# ADC_2CH.net
KiCad netlist of a schematic drawn in Altium Designer
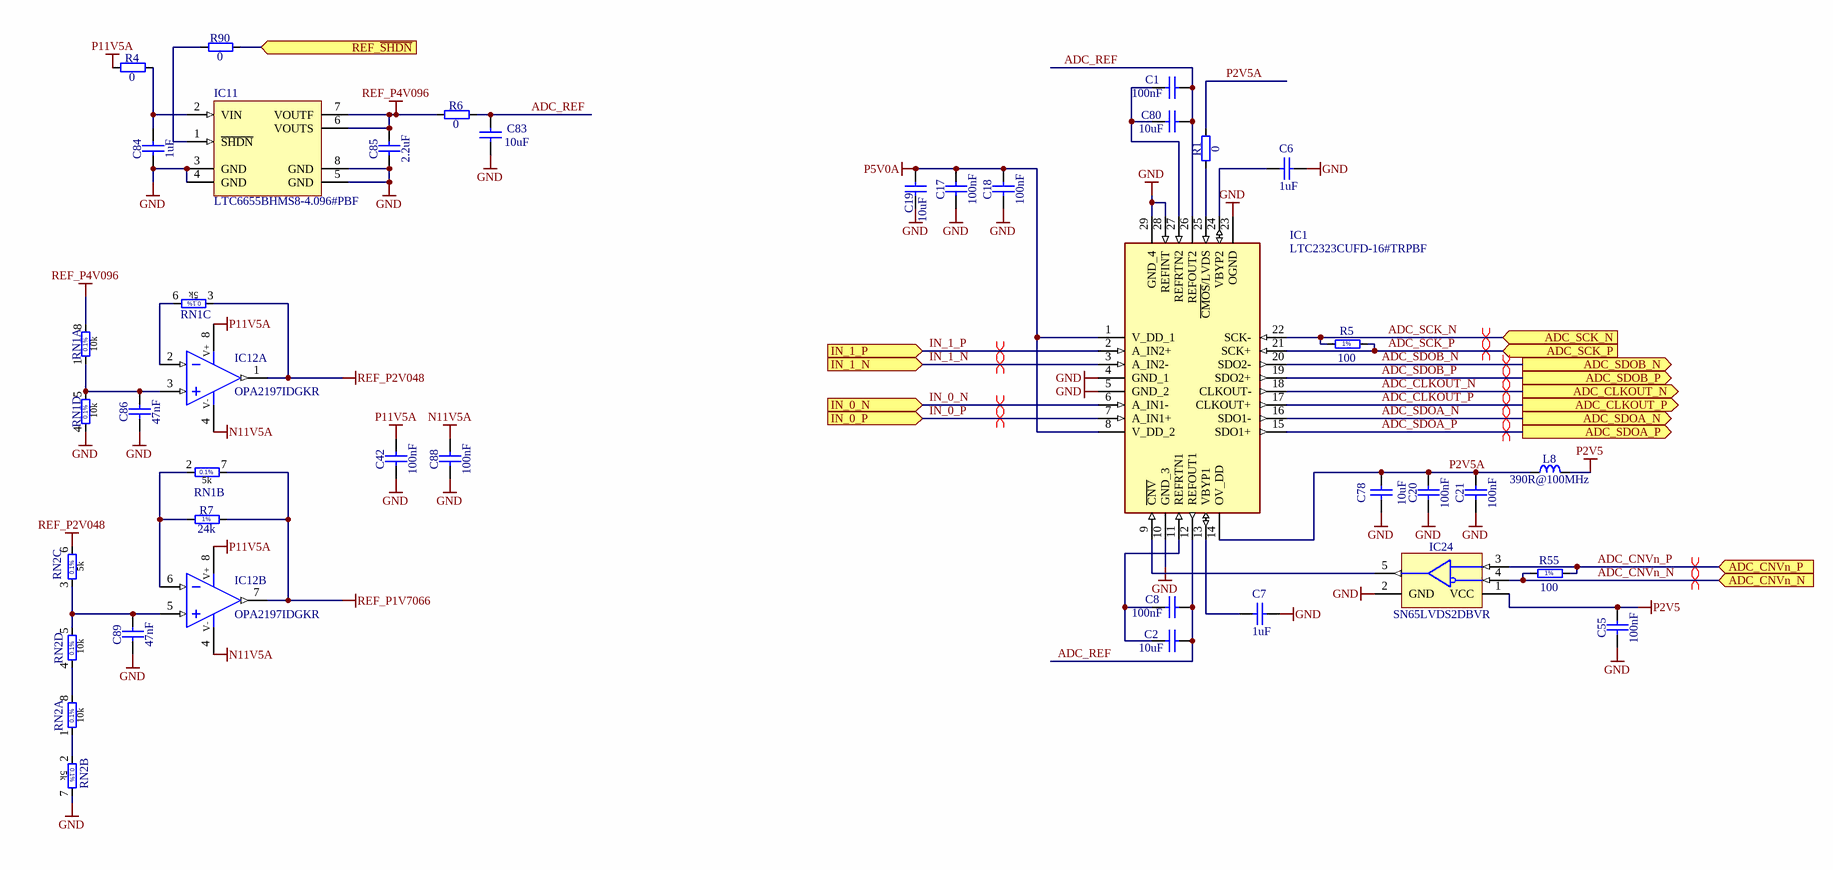
[diagram p0: ADC_2CH.SchDoc]

(export (version "E")
  (design (tool "Eeschema 10.0.6"))
  (components
    (comp (ref "C1")
      (value "100nF")
      (footprint "CAPC1608X87N")
      (description "Non-polarised capacitor")
      (fields
        (field (name "PART NUMBER") "CC0603_100NF_50V_10%_X7R")
        (field (name "VOLTAGE") "50V")
        (field (name "AUTHOR") "CERN DEM JLC")
      )
      (libsource (lib "Capacitors") (part "Capacitor - non polarized"))
    )
    (comp (ref "C2")
      (value "10uF")
      (footprint "CAPC2012X95N")
      (description "Non-polarised capacitor")
      (fields
        (field (name "PART NUMBER") "CC0805_10UF_25V_10%_X5R")
        (field (name "VOLTAGE") "25V")
        (field (name "AUTHOR") "CERN DEM JLC")
      )
      (libsource (lib "Capacitors") (part "Capacitor - non polarized"))
    )
    (comp (ref "C6")
      (value "1uF")
      (footprint "CAPC1608X87N")
      (description "Non-polarised capacitor")
      (fields
        (field (name "PART NUMBER") "CC0603_1UF_25V_10%_X7R")
        (field (name "VOLTAGE") "25V")
        (field (name "AUTHOR") "CERN DEM JLC")
      )
      (libsource (lib "Capacitors") (part "Capacitor - non polarized"))
    )
    (comp (ref "C7")
      (value "1uF")
      (footprint "CAPC1608X87N")
      (description "Non-polarised capacitor")
      (fields
        (field (name "PART NUMBER") "CC0603_1UF_25V_10%_X7R")
        (field (name "VOLTAGE") "25V")
        (field (name "AUTHOR") "CERN DEM JLC")
      )
      (libsource (lib "Capacitors") (part "Capacitor - non polarized"))
    )
    (comp (ref "C8")
      (value "100nF")
      (footprint "CAPC1608X87N")
      (description "Non-polarised capacitor")
      (fields
        (field (name "PART NUMBER") "CC0603_100NF_50V_10%_X7R")
        (field (name "VOLTAGE") "50V")
        (field (name "AUTHOR") "CERN DEM JLC")
      )
      (libsource (lib "Capacitors") (part "Capacitor - non polarized"))
    )
    (comp (ref "C17")
      (value "100nF")
      (footprint "CAPC1608X87N")
      (description "Non-polarised capacitor")
      (fields
        (field (name "PART NUMBER") "CC0603_100NF_50V_10%_X7R")
        (field (name "VOLTAGE") "50V")
        (field (name "AUTHOR") "CERN DEM JLC")
      )
      (libsource (lib "Capacitors") (part "Capacitor - non polarized"))
    )
    (comp (ref "C18")
      (value "100nF")
      (footprint "CAPC1608X87N")
      (description "Non-polarised capacitor")
      (fields
        (field (name "PART NUMBER") "CC0603_100NF_50V_10%_X7R")
        (field (name "VOLTAGE") "50V")
        (field (name "AUTHOR") "CERN DEM JLC")
      )
      (libsource (lib "Capacitors") (part "Capacitor - non polarized"))
    )
    (comp (ref "C19")
      (value "10uF")
      (footprint "CAPC2012X95N")
      (description "Non-polarised capacitor")
      (fields
        (field (name "PART NUMBER") "CC0805_10UF_25V_10%_X5R")
        (field (name "VOLTAGE") "25V")
        (field (name "AUTHOR") "CERN DEM JLC")
      )
      (libsource (lib "Capacitors") (part "Capacitor - non polarized"))
    )
    (comp (ref "C20")
      (value "100nF")
      (footprint "CAPC1608X87N")
      (description "Non-polarised capacitor")
      (fields
        (field (name "PART NUMBER") "CC0603_100NF_50V_10%_X7R")
        (field (name "VOLTAGE") "50V")
        (field (name "AUTHOR") "CERN DEM JLC")
      )
      (libsource (lib "Capacitors") (part "Capacitor - non polarized"))
    )
    (comp (ref "C21")
      (value "100nF")
      (footprint "CAPC1608X87N")
      (description "Non-polarised capacitor")
      (fields
        (field (name "PART NUMBER") "CC0603_100NF_50V_10%_X7R")
        (field (name "VOLTAGE") "50V")
        (field (name "AUTHOR") "CERN DEM JLC")
      )
      (libsource (lib "Capacitors") (part "Capacitor - non polarized"))
    )
    (comp (ref "C42")
      (value "100nF")
      (footprint "CAPC1005X55N")
      (description "Non-polarised capacitor")
      (fields
        (field (name "PART NUMBER") "CC0402_100NF_16V_10%_X5R")
        (field (name "VOLTAGE") "16V")
        (field (name "AUTHOR") "CERN DEM JLC")
      )
      (libsource (lib "Capacitors") (part "Capacitor - non polarized"))
    )
    (comp (ref "C55")
      (value "100nF")
      (footprint "CAPC1608X87N")
      (description "Non-polarised capacitor")
      (fields
        (field (name "PART NUMBER") "CC0603_100NF_50V_10%_X7R")
        (field (name "VOLTAGE") "50V")
        (field (name "AUTHOR") "CERN DEM JLC")
      )
      (libsource (lib "Capacitors") (part "Capacitor - non polarized"))
    )
    (comp (ref "C78")
      (value "10uF")
      (footprint "CAPC2012X95N")
      (description "Non-polarised capacitor")
      (fields
        (field (name "PART NUMBER") "CC0805_10UF_25V_10%_X5R")
        (field (name "VOLTAGE") "25V")
        (field (name "AUTHOR") "CERN DEM JLC")
      )
      (libsource (lib "Capacitors") (part "Capacitor - non polarized"))
    )
    (comp (ref "C80")
      (value "10uF")
      (footprint "CAPC2012X95N")
      (description "Non-polarised capacitor")
      (fields
        (field (name "PART NUMBER") "CC0805_10UF_25V_10%_X5R")
        (field (name "VOLTAGE") "25V")
        (field (name "AUTHOR") "CERN DEM JLC")
      )
      (libsource (lib "Capacitors") (part "Capacitor - non polarized"))
    )
    (comp (ref "C83")
      (value "10uF")
      (footprint "CAPC2012X95N")
      (description "Non-polarised capacitor")
      (fields
        (field (name "PART NUMBER") "CC0805_10UF_25V_10%_X5R")
        (field (name "VOLTAGE") "25V")
        (field (name "AUTHOR") "CERN DEM JLC")
      )
      (libsource (lib "Capacitors") (part "Capacitor - non polarized"))
    )
    (comp (ref "C84")
      (value "1uF")
      (footprint "CAPC1608X87N")
      (description "Non-polarised capacitor")
      (fields
        (field (name "PART NUMBER") "CC0603_1UF_25V_10%_X7R")
        (field (name "VOLTAGE") "25V")
        (field (name "AUTHOR") "CERN DEM JLC")
      )
      (libsource (lib "Capacitors") (part "Capacitor - non polarized"))
    )
    (comp (ref "C85")
      (value "2.2uF")
      (footprint "CAPC1608X87N")
      (description "Non-polarised capacitor")
      (fields
        (field (name "PART NUMBER") "CC0603_2.2UF_16V_10%_X5R")
        (field (name "VOLTAGE") "16V")
        (field (name "AUTHOR") "CERN DEM JLC")
      )
      (libsource (lib "Capacitors") (part "Capacitor - non polarized"))
    )
    (comp (ref "C86")
      (value "47nF")
      (footprint "CAPC2012X135N")
      (description "Non-polarised capacitor")
      (fields
        (field (name "PART NUMBER") "CC0805_47NF_25V_5%_C0G")
        (field (name "VOLTAGE") "25V")
        (field (name "AUTHOR") "CERN DEM JLC")
      )
      (libsource (lib "Capacitors") (part "Capacitor - non polarized"))
    )
    (comp (ref "C88")
      (value "100nF")
      (footprint "CAPC1005X55N")
      (description "Non-polarised capacitor")
      (fields
        (field (name "PART NUMBER") "CC0402_100NF_16V_10%_X5R")
        (field (name "VOLTAGE") "16V")
        (field (name "AUTHOR") "CERN DEM JLC")
      )
      (libsource (lib "Capacitors") (part "Capacitor - non polarized"))
    )
    (comp (ref "C89")
      (value "47nF")
      (footprint "CAPC2012X135N")
      (description "Non-polarised capacitor")
      (fields
        (field (name "PART NUMBER") "CC0805_47NF_25V_5%_C0G")
        (field (name "VOLTAGE") "25V")
        (field (name "AUTHOR") "CERN DEM JLC")
      )
      (libsource (lib "Capacitors") (part "Capacitor - non polarized"))
    )
    (comp (ref "IC1")
      (value "LTC2323CUFD-16#TRPBF")
      (footprint "SamacSys:QFN50P400X500X80-29N")
      (description "Integrated Circuit")
      (libsource (lib "*") (part "LTC2323CUFD-16#TRPBF"))
    )
    (comp (ref "IC11")
      (value "LTC6655BHMS8-4.096#PBF")
      (footprint "SOP65P490X110-8N")
      (description "0.25ppm Noise, Low Drift Precision Buffered Voltage Reference")
      (fields (field (name "MANUFACTURER") "LINEAR TECHNOLOGY") (field (name "AUTHOR") "GK"))
      (libsource (lib "LIBRARY_SCH") (part "REF_LTC6655"))
    )
    (comp (ref "IC12")
      (value "OPA2197IDGKR")
      (footprint "SOP65P490X110-8N")
      (description "36-V, Precision, Rail-to-Rail Input Output, Low Offset Voltage Op Amp 8-VSSOP")
      (fields (field (name "MANUFACTURER") "TEXAS INSTRUMENTS") (field (name "AUTHOR") "GK"))
      (libsource (lib "LIBRARY_SCH") (part "OA_OPA2197IDGKR"))
    )
    (comp (ref "IC24")
      (value "SN65LVDS2DBVR")
      (footprint "SOT95P280X145-5N")
      (description "High-Speed Differential Line Receiver")
      (fields (field (name "MANUFACTURER") "TEXAS INSTRUMENTS") (field (name "AUTHOR") "CERN DEM JLC"))
      (libsource (lib "ICs And Semiconductors") (part "SN65LVDS2DBV"))
    )
    (comp (ref "L8")
      (value "390R@100MHz")
      (footprint "INDC1608X95N")
      (description "Inductor")
      (fields
        (field (name "PART NUMBER") "IND0603_TDK_MPZ1608R391A")
        (field (name "POWER") "1.2A")
        (field (name "AUTHOR") "CERN DEM JLC")
      )
      (libsource (lib "Inductors & Transformers") (part "Inductor"))
    )
    (comp (ref "R1")
      (value "0")
      (footprint "RESC1005X40N")
      (description "Resistor")
      (fields
        (field (name "PART NUMBER") "R0402_0R_JUMPER")
        (field (name "MANUFACTURER") "GENERIC")
        (field (name "AUTHOR") "CERN DEM JLC")
      )
      (libsource (lib "Resistors") (part "Resistor"))
    )
    (comp (ref "R4")
      (value "0")
      (footprint "RESC1005X40N")
      (description "Resistor")
      (fields
        (field (name "PART NUMBER") "R0402_0R_JUMPER")
        (field (name "MANUFACTURER") "GENERIC")
        (field (name "AUTHOR") "CERN DEM JLC")
      )
      (libsource (lib "Resistors") (part "Resistor"))
    )
    (comp (ref "R5")
      (value "100")
      (footprint "RESC1005X40N")
      (description "Resistor - 1%")
      (fields
        (field (name "PART NUMBER") "R0402_100R_1%_0.1W_100PPM")
        (field (name "POWER") "0.1W")
        (field (name "AUTHOR") "CERN DEM JLC")
      )
      (libsource (lib "Resistors") (part "Resistor - 1%"))
    )
    (comp (ref "R6")
      (value "0")
      (footprint "RESC1005X40N")
      (description "Resistor")
      (fields
        (field (name "PART NUMBER") "R0402_0R_JUMPER")
        (field (name "MANUFACTURER") "GENERIC")
        (field (name "AUTHOR") "CERN DEM JLC")
      )
      (libsource (lib "Resistors") (part "Resistor"))
    )
    (comp (ref "R7")
      (value "24k")
      (footprint "RESC1608X55N")
      (description "Resistor - 1%")
      (fields
        (field (name "PART NUMBER") "R0603_24K_1%_0.1W_100PPM")
        (field (name "POWER") "0.1W")
        (field (name "AUTHOR") "CERN DEM JLC")
      )
      (libsource (lib "Resistors") (part "Resistor - 1%"))
    )
    (comp (ref "R55")
      (value "100")
      (footprint "RESC1005X40N")
      (description "Resistor - 1%")
      (fields
        (field (name "PART NUMBER") "R0402_100R_1%_0.1W_100PPM")
        (field (name "POWER") "0.1W")
        (field (name "AUTHOR") "CERN DEM JLC")
      )
      (libsource (lib "Resistors") (part "Resistor - 1%"))
    )
    (comp (ref "R90")
      (value "0")
      (footprint "RESC1005X40N")
      (description "Resistor")
      (fields
        (field (name "PART NUMBER") "R0402_0R_JUMPER")
        (field (name "MANUFACTURER") "GENERIC")
        (field (name "AUTHOR") "CERN DEM JLC")
      )
      (libsource (lib "Resistors") (part "Resistor"))
    )
    (comp (ref "RN1")
      (value "10k 5K 5K 10K")
      (footprint "SOIC127P600X175-8N")
      (description "DIL8 Resistor Network 4 Resistors 10k-5k-5k-10k 0.1%")
      (fields
        (field (name "PART NUMBER") "RN_10K_5K_VISHAY_AORN2-1AT3")
        (field (name "POWER") "4x0.1W")
        (field (name "AUTHOR") "CERN DEM JLC")
      )
      (libsource (lib "Resistors") (part "RN DIL8_4xR_10k-5k-5k-10k_0.1%"))
    )
    (comp (ref "RN2")
      (value "10k 5K 5K 10K")
      (footprint "SOIC127P600X175-8N")
      (description "DIL8 Resistor Network 4 Resistors 10k-5k-5k-10k 0.1%")
      (fields
        (field (name "PART NUMBER") "RN_10K_5K_VISHAY_AORN2-1AT3")
        (field (name "POWER") "4x0.1W")
        (field (name "AUTHOR") "CERN DEM JLC")
      )
      (libsource (lib "Resistors") (part "RN DIL8_4xR_10k-5k-5k-10k_0.1%"))
    )
  )
  (nets
    (net (code "1") (name "/ADC_CLKOUT_N") (class "Default")
      (node (ref "IC1") (pin "18") (pinfunction "CLKOUT-_18") (pintype "output"))
    )
    (net (code "2") (name "/ADC_CLKOUT_P") (class "Default")
      (node (ref "IC1") (pin "17") (pinfunction "CLKOUT+_17") (pintype "output"))
    )
    (net (code "3") (name "/ADC_CNVn_N") (class "Default")
      (node (ref "IC24") (pin "4") (pinfunction "B_4") (pintype "input"))
      (node (ref "R55") (pin "1") (pinfunction "1_1") (pintype "passive"))
    )
    (net (code "4") (name "/ADC_CNVn_P") (class "Default")
      (node (ref "IC24") (pin "3") (pinfunction "A_3") (pintype "input"))
      (node (ref "R55") (pin "2") (pinfunction "2_2") (pintype "passive"))
    )
    (net (code "5") (name "/ADC_REF") (class "Default")
      (node (ref "C1") (pin "1") (pinfunction "1_1") (pintype "passive"))
      (node (ref "C2") (pin "2") (pinfunction "2_2") (pintype "passive"))
      (node (ref "C8") (pin "1") (pinfunction "1_1") (pintype "passive"))
      (node (ref "C80") (pin "2") (pinfunction "2_2") (pintype "passive"))
      (node (ref "C83") (pin "2") (pinfunction "2_2") (pintype "passive"))
      (node (ref "IC1") (pin "12") (pinfunction "REFOUT1_12") (pintype "output"))
      (node (ref "IC1") (pin "26") (pinfunction "REFOUT2_26") (pintype "power_in"))
      (node (ref "R6") (pin "2") (pinfunction "2_2") (pintype "passive"))
    )
    (net (code "6") (name "/ADC_SCK_N") (class "Default")
      (node (ref "IC1") (pin "22") (pinfunction "SCK-_22") (pintype "input"))
      (node (ref "R5") (pin "1") (pinfunction "1_1") (pintype "passive"))
    )
    (net (code "7") (name "/ADC_SCK_P") (class "Default")
      (node (ref "IC1") (pin "21") (pinfunction "SCK+_21") (pintype "input"))
      (node (ref "R5") (pin "2") (pinfunction "2_2") (pintype "passive"))
    )
    (net (code "8") (name "/ADC_SDOA_N") (class "Default")
      (node (ref "IC1") (pin "16") (pinfunction "SDO1-_16") (pintype "output"))
    )
    (net (code "9") (name "/ADC_SDOA_P") (class "Default")
      (node (ref "IC1") (pin "15") (pinfunction "SDO1+_15") (pintype "output"))
    )
    (net (code "10") (name "/ADC_SDOB_N") (class "Default")
      (node (ref "IC1") (pin "20") (pinfunction "SDO2-_20") (pintype "output"))
    )
    (net (code "11") (name "/ADC_SDOB_P") (class "Default")
      (node (ref "IC1") (pin "19") (pinfunction "SDO2+_19") (pintype "output"))
    )
    (net (code "12") (name "/IN_0_N") (class "Default")
      (node (ref "IC1") (pin "6") (pinfunction "A_IN1-_6") (pintype "input"))
    )
    (net (code "13") (name "/IN_0_P") (class "Default")
      (node (ref "IC1") (pin "7") (pinfunction "A_IN1+_7") (pintype "input"))
    )
    (net (code "14") (name "/IN_1_N") (class "Default")
      (node (ref "IC1") (pin "3") (pinfunction "A_IN2-_3") (pintype "input"))
    )
    (net (code "15") (name "/IN_1_P") (class "Default")
      (node (ref "IC1") (pin "2") (pinfunction "A_IN2+_2") (pintype "input"))
    )
    (net (code "16") (name "/P2V5A") (class "Default")
      (node (ref "C20") (pin "2") (pinfunction "2_2") (pintype "passive"))
      (node (ref "C21") (pin "2") (pinfunction "2_2") (pintype "passive"))
      (node (ref "C78") (pin "2") (pinfunction "2_2") (pintype "passive"))
      (node (ref "IC1") (pin "14") (pinfunction "OV_DD_14") (pintype "power_in"))
      (node (ref "L8") (pin "1") (pinfunction "1_1") (pintype "passive"))
      (node (ref "R1") (pin "2") (pinfunction "2_2") (pintype "passive"))
    )
    (net (code "17") (name "/REF_~{SHDN}") (class "Default")
      (node (ref "R90") (pin "2") (pinfunction "2_2") (pintype "passive"))
    )
    (net (code "18") (name "GND") (class "Default")
      (node (ref "C17") (pin "1") (pinfunction "1_1") (pintype "passive"))
      (node (ref "C18") (pin "1") (pinfunction "1_1") (pintype "passive"))
      (node (ref "C19") (pin "1") (pinfunction "1_1") (pintype "passive"))
      (node (ref "C20") (pin "1") (pinfunction "1_1") (pintype "passive"))
      (node (ref "C21") (pin "1") (pinfunction "1_1") (pintype "passive"))
      (node (ref "C42") (pin "1") (pinfunction "1_1") (pintype "passive"))
      (node (ref "C55") (pin "1") (pinfunction "1_1") (pintype "passive"))
      (node (ref "C6") (pin "1") (pinfunction "1_1") (pintype "passive"))
      (node (ref "C7") (pin "1") (pinfunction "1_1") (pintype "passive"))
      (node (ref "C78") (pin "1") (pinfunction "1_1") (pintype "passive"))
      (node (ref "C83") (pin "1") (pinfunction "1_1") (pintype "passive"))
      (node (ref "C84") (pin "1") (pinfunction "1_1") (pintype "passive"))
      (node (ref "C85") (pin "1") (pinfunction "1_1") (pintype "passive"))
      (node (ref "C86") (pin "1") (pinfunction "1_1") (pintype "passive"))
      (node (ref "C88") (pin "1") (pinfunction "1_1") (pintype "passive"))
      (node (ref "C89") (pin "1") (pinfunction "1_1") (pintype "passive"))
      (node (ref "IC1") (pin "10") (pinfunction "GND_3_10") (pintype "power_in"))
      (node (ref "IC1") (pin "23") (pinfunction "OGND_23") (pintype "power_in"))
      (node (ref "IC1") (pin "28") (pinfunction "REFINT_28") (pintype "input"))
      (node (ref "IC1") (pin "29") (pinfunction "GND_4_29") (pintype "power_in"))
      (node (ref "IC1") (pin "4") (pinfunction "GND_1_4") (pintype "power_in"))
      (node (ref "IC1") (pin "5") (pinfunction "GND_2_5") (pintype "power_in"))
      (node (ref "IC11") (pin "3") (pinfunction "GND_3") (pintype "power_in"))
      (node (ref "IC11") (pin "4") (pinfunction "GND_4") (pintype "power_in"))
      (node (ref "IC11") (pin "5") (pinfunction "GND_5") (pintype "power_in"))
      (node (ref "IC11") (pin "8") (pinfunction "GND_8") (pintype "power_in"))
      (node (ref "IC24") (pin "2") (pinfunction "GND_2") (pintype "power_in"))
      (node (ref "RN1") (pin "4") (pinfunction "4_4") (pintype "passive"))
      (node (ref "RN2") (pin "7") (pinfunction "7_7") (pintype "passive"))
    )
    (net (code "19") (name "N11V5A") (class "Default")
      (node (ref "C88") (pin "2") (pinfunction "2_2") (pintype "passive"))
      (node (ref "IC12") (pin "4") (pinfunction "V-_4") (pintype "power_in"))
    )
    (net (code "20") (name "Net-(IC1-REFRTN1)") (class "Default")
      (node (ref "C2") (pin "1") (pinfunction "1_1") (pintype "passive"))
      (node (ref "C8") (pin "2") (pinfunction "2_2") (pintype "passive"))
      (node (ref "IC1") (pin "11") (pinfunction "REFRTN1_11") (pintype "input"))
    )
    (net (code "21") (name "Net-(IC1-REFRTN2)") (class "Default")
      (node (ref "C1") (pin "2") (pinfunction "2_2") (pintype "passive"))
      (node (ref "C80") (pin "1") (pinfunction "1_1") (pintype "passive"))
      (node (ref "IC1") (pin "27") (pinfunction "REFRTN2_27") (pintype "input"))
    )
    (net (code "22") (name "Net-(IC1-VBYP1)") (class "Default")
      (node (ref "C7") (pin "2") (pinfunction "2_2") (pintype "passive"))
      (node (ref "IC1") (pin "13") (pinfunction "VBYP1_13") (pintype "bidirectional"))
    )
    (net (code "23") (name "Net-(IC1-VBYP2)") (class "Default")
      (node (ref "C6") (pin "2") (pinfunction "2_2") (pintype "passive"))
      (node (ref "IC1") (pin "24") (pinfunction "VBYP2_24") (pintype "bidirectional"))
    )
    (net (code "24") (name "Net-(IC1-~{CMOS}{slash}LVDS)") (class "Default")
      (node (ref "IC1") (pin "25") (pinfunction "~{CMOS}/LVDS_25") (pintype "input"))
      (node (ref "R1") (pin "1") (pinfunction "1_1") (pintype "passive"))
    )
    (net (code "25") (name "Net-(IC1-~{CNV})") (class "Default")
      (node (ref "IC1") (pin "9") (pinfunction "~{CNV}_9") (pintype "input"))
      (node (ref "IC24") (pin "5") (pinfunction "R_5") (pintype "output"))
    )
    (net (code "26") (name "Net-(IC11-VIN)") (class "Default")
      (node (ref "C84") (pin "2") (pinfunction "2_2") (pintype "passive"))
      (node (ref "IC11") (pin "2") (pinfunction "VIN_2") (pintype "input"))
      (node (ref "R4") (pin "2") (pinfunction "2_2") (pintype "passive"))
    )
    (net (code "27") (name "Net-(IC11-~{SHDN})") (class "Default")
      (node (ref "IC11") (pin "1") (pinfunction "~{SHDN}_1") (pintype "input"))
      (node (ref "R90") (pin "1") (pinfunction "1_1") (pintype "passive"))
    )
    (net (code "28") (name "Net-(IC12A-IN+)") (class "Default")
      (node (ref "C86") (pin "2") (pinfunction "2_2") (pintype "passive"))
      (node (ref "IC12") (pin "3") (pinfunction "IN+_3") (pintype "input"))
      (node (ref "RN1") (pin "1") (pinfunction "1_1") (pintype "passive"))
      (node (ref "RN1") (pin "5") (pinfunction "5_5") (pintype "passive"))
    )
    (net (code "29") (name "Net-(IC12A-IN-)") (class "Default")
      (node (ref "IC12") (pin "2") (pinfunction "IN-_2") (pintype "input"))
      (node (ref "RN1") (pin "6") (pinfunction "6_6") (pintype "passive"))
    )
    (net (code "30") (name "Net-(IC12B-IN+)") (class "Default")
      (node (ref "C89") (pin "2") (pinfunction "2_2") (pintype "passive"))
      (node (ref "IC12") (pin "5") (pinfunction "IN+_5") (pintype "input"))
      (node (ref "RN2") (pin "3") (pinfunction "3_3") (pintype "passive"))
      (node (ref "RN2") (pin "5") (pinfunction "5_5") (pintype "passive"))
    )
    (net (code "31") (name "Net-(IC12B-IN-)") (class "Default")
      (node (ref "IC12") (pin "6") (pinfunction "IN-_6") (pintype "input"))
      (node (ref "R7") (pin "1") (pinfunction "1_1") (pintype "passive"))
      (node (ref "RN1") (pin "2") (pinfunction "2_2") (pintype "passive"))
    )
    (net (code "32") (name "Net-(RN2-Pad1)") (class "Default")
      (node (ref "RN2") (pin "1") (pinfunction "1_1") (pintype "passive"))
      (node (ref "RN2") (pin "2") (pinfunction "2_2") (pintype "passive"))
    )
    (net (code "33") (name "Net-(RN2-Pad4)") (class "Default")
      (node (ref "RN2") (pin "4") (pinfunction "4_4") (pintype "passive"))
      (node (ref "RN2") (pin "8") (pinfunction "8_8") (pintype "passive"))
    )
    (net (code "34") (name "P2V5") (class "Default")
      (node (ref "C55") (pin "2") (pinfunction "2_2") (pintype "passive"))
      (node (ref "IC24") (pin "1") (pinfunction "VCC_1") (pintype "power_in"))
      (node (ref "L8") (pin "2") (pinfunction "2_2") (pintype "passive"))
    )
    (net (code "35") (name "P5V0A") (class "Default")
      (node (ref "C17") (pin "2") (pinfunction "2_2") (pintype "passive"))
      (node (ref "C18") (pin "2") (pinfunction "2_2") (pintype "passive"))
      (node (ref "C19") (pin "2") (pinfunction "2_2") (pintype "passive"))
      (node (ref "IC1") (pin "1") (pinfunction "V_DD_1_1") (pintype "power_in"))
      (node (ref "IC1") (pin "8") (pinfunction "V_DD_2_8") (pintype "power_in"))
    )
    (net (code "36") (name "P11V5A") (class "Default")
      (node (ref "C42") (pin "2") (pinfunction "2_2") (pintype "passive"))
      (node (ref "IC12") (pin "8") (pinfunction "V+_8") (pintype "power_in"))
      (node (ref "R4") (pin "1") (pinfunction "1_1") (pintype "passive"))
    )
    (net (code "37") (name "REF_P1V7066") (class "Default")
      (node (ref "IC12") (pin "7") (pinfunction "OUT_7") (pintype "output"))
      (node (ref "R7") (pin "2") (pinfunction "2_2") (pintype "passive"))
      (node (ref "RN1") (pin "7") (pinfunction "7_7") (pintype "passive"))
    )
    (net (code "38") (name "REF_P2V048") (class "Default")
      (node (ref "IC12") (pin "1") (pinfunction "OUT_1") (pintype "output"))
      (node (ref "RN1") (pin "3") (pinfunction "3_3") (pintype "passive"))
      (node (ref "RN2") (pin "6") (pinfunction "6_6") (pintype "passive"))
    )
    (net (code "39") (name "REF_P4V096") (class "Default")
      (node (ref "C85") (pin "2") (pinfunction "2_2") (pintype "passive"))
      (node (ref "IC11") (pin "6") (pinfunction "VOUTS_6") (pintype "power_in"))
      (node (ref "IC11") (pin "7") (pinfunction "VOUTF_7") (pintype "power_in"))
      (node (ref "R6") (pin "1") (pinfunction "1_1") (pintype "passive"))
      (node (ref "RN1") (pin "8") (pinfunction "8_8") (pintype "passive"))
    )
  )
)
